# 2021-06-24.net
KiCad netlist of a schematic drawn in EasyEDA
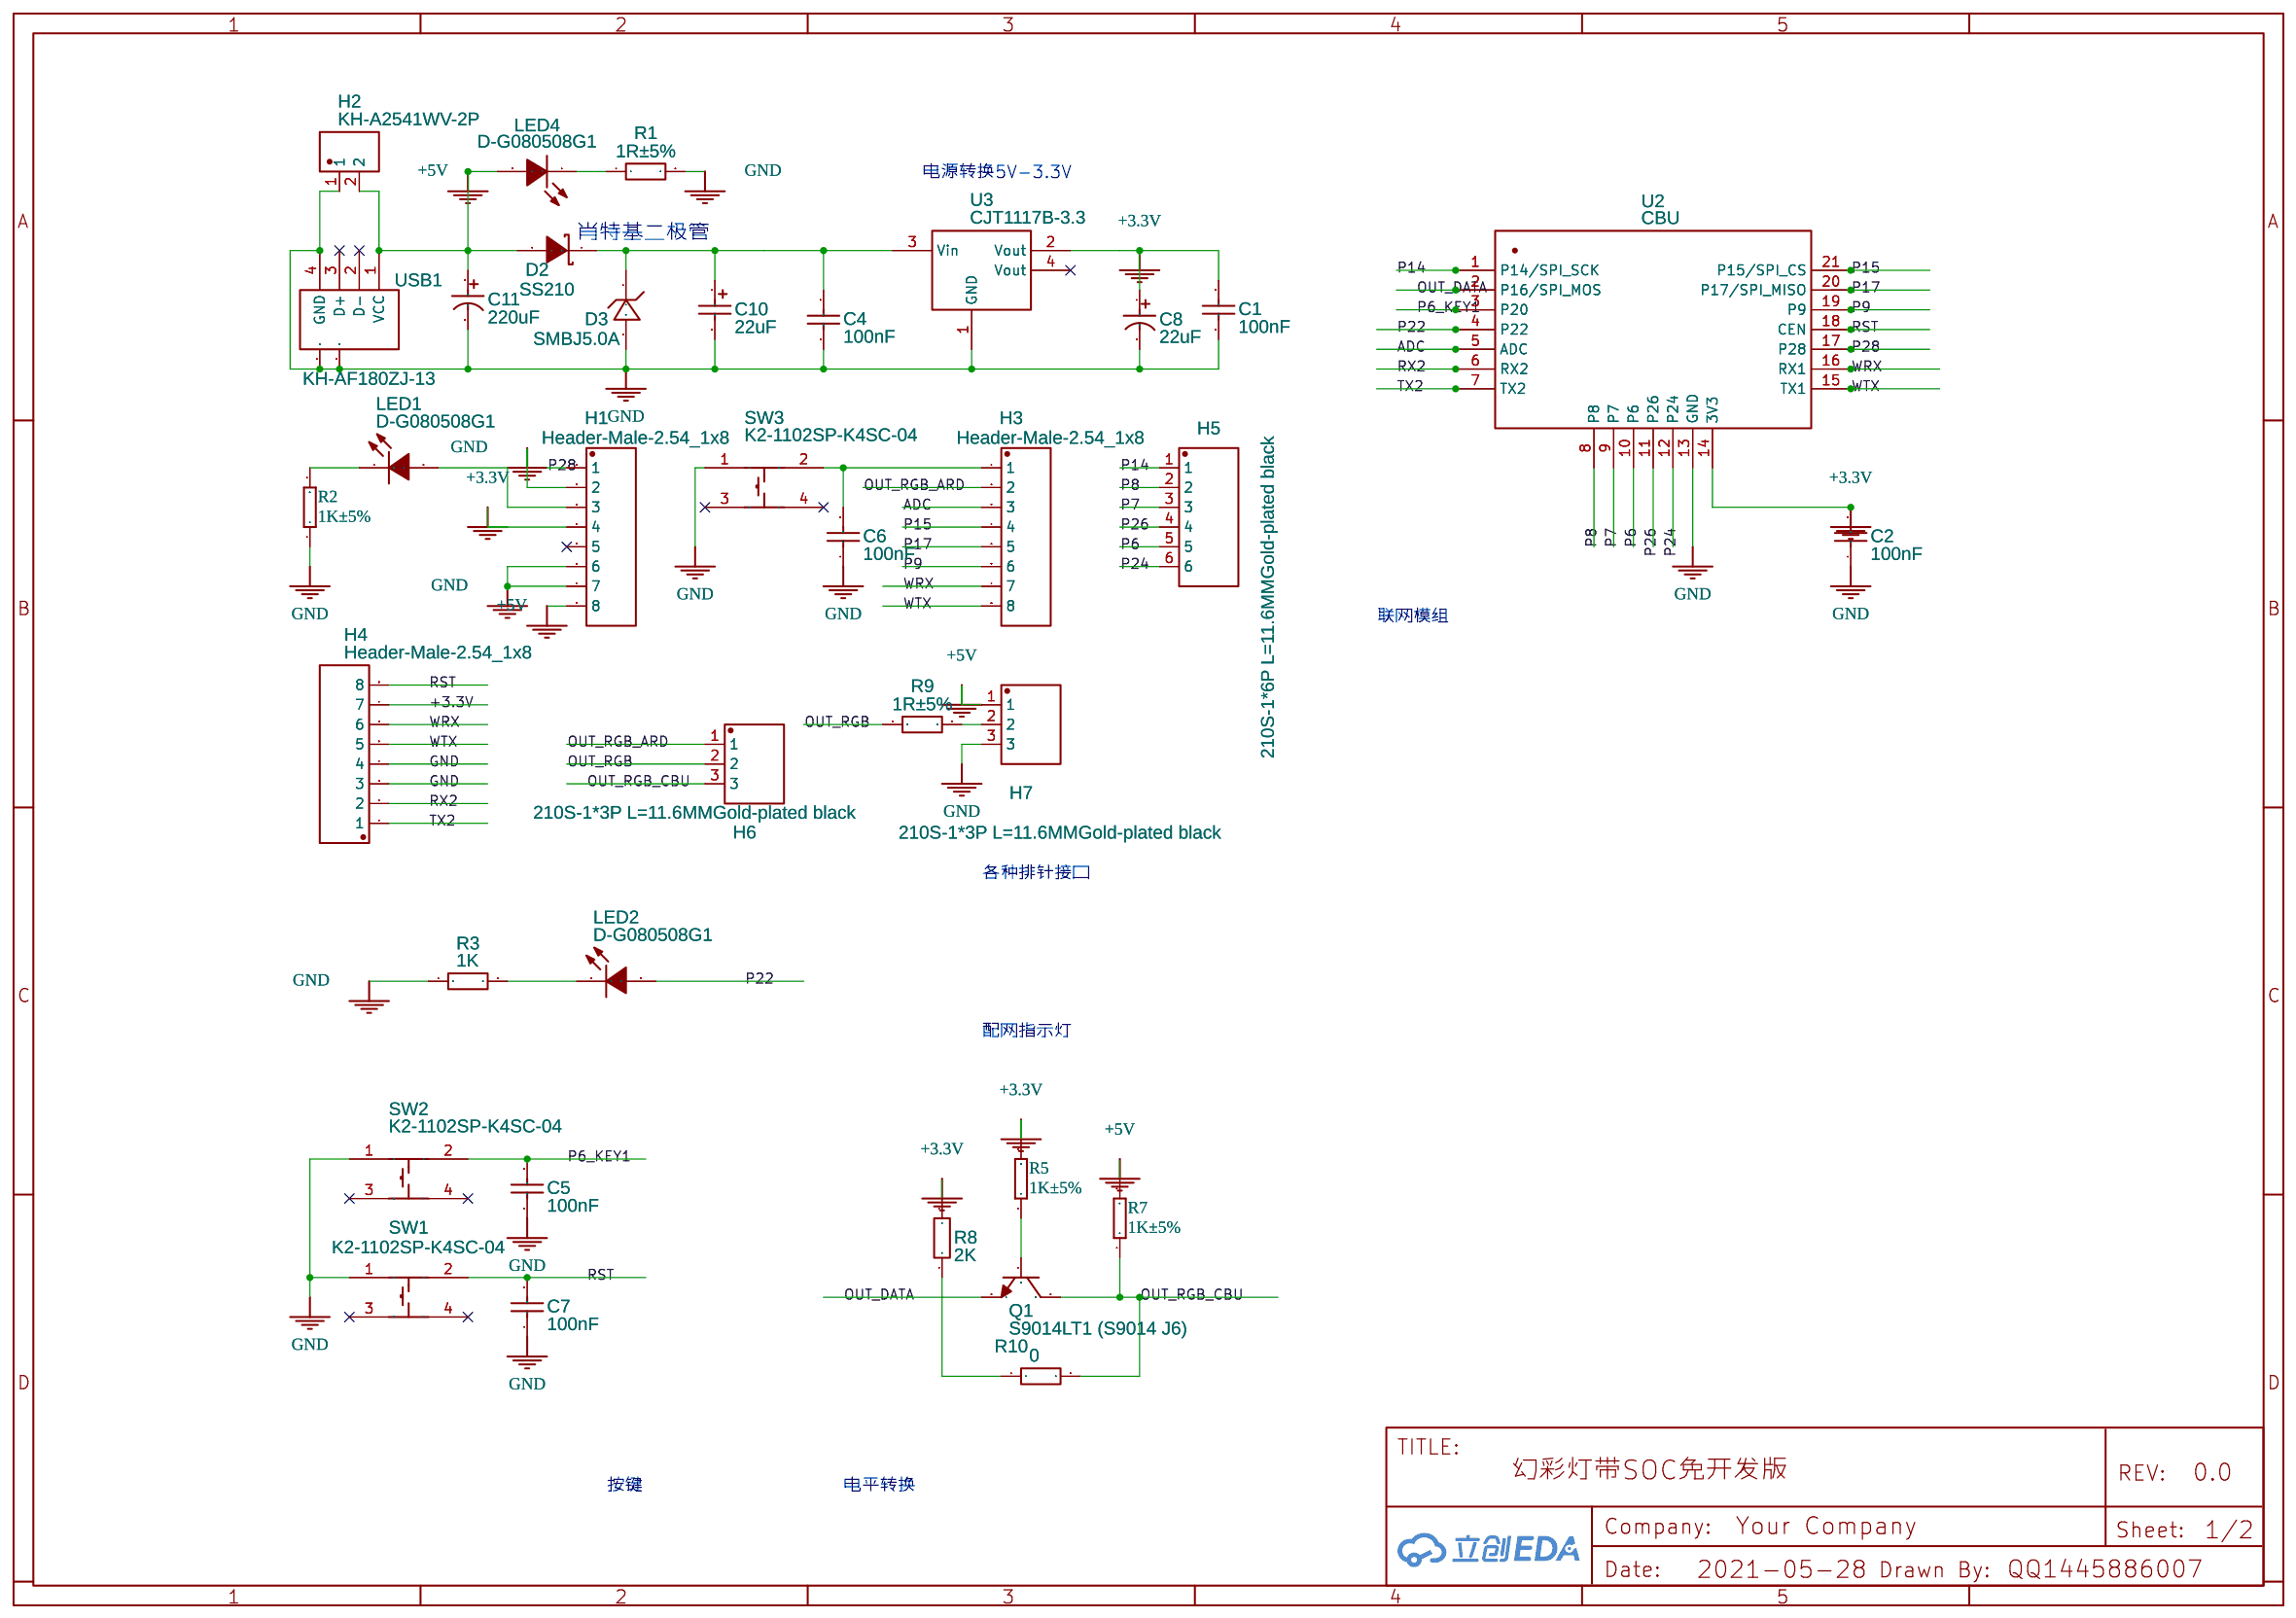
[diagram p0: schematic sheet]

(export (version "E")
  (design (tool "Eeschema 10.0.6"))
  (components
    (comp (ref "C1")
      (value "100nF")
      (fields
        (field (name "BOM_Manufacturer Part") "CL10F104ZA8NNNC")
        (field (name "BOM_Supplier Part") "C95838")
      )
      (libsource (lib "") (part "CL10F104ZA8NNNC"))
    )
    (comp (ref "C2")
      (value "100nF")
      (fields
        (field (name "BOM_Manufacturer Part") "CL10F104ZA8NNNC")
        (field (name "BOM_Supplier Part") "C95838")
      )
      (libsource (lib "") (part "CL10F104ZA8NNNC"))
    )
    (comp (ref "C4")
      (value "100nF")
      (fields
        (field (name "BOM_Manufacturer Part") "CL10F104ZA8NNNC")
        (field (name "BOM_Supplier Part") "C95838")
      )
      (libsource (lib "") (part "CL10F104ZA8NNNC"))
    )
    (comp (ref "C5")
      (value "100nF")
      (fields
        (field (name "BOM_Manufacturer Part") "CL10F104ZA8NNNC")
        (field (name "BOM_Supplier Part") "C95838")
      )
      (libsource (lib "") (part "CL10F104ZA8NNNC"))
    )
    (comp (ref "C6")
      (value "100nF")
      (fields
        (field (name "BOM_Manufacturer Part") "CL10F104ZA8NNNC")
        (field (name "BOM_Supplier Part") "C95838")
      )
      (libsource (lib "") (part "CL10F104ZA8NNNC"))
    )
    (comp (ref "C7")
      (value "100nF")
      (fields
        (field (name "BOM_Manufacturer Part") "CL10F104ZA8NNNC")
        (field (name "BOM_Supplier Part") "C95838")
      )
      (libsource (lib "") (part "CL10F104ZA8NNNC"))
    )
    (comp (ref "C8")
      (value "22uF")
      (fields
        (field (name "BOM_Manufacturer Part") "KS1C220MB070A00CV0")
        (field (name "BOM_Supplier Part") "C216316")
      )
      (libsource (lib "") (part "KS1C220MB070A00CV0"))
    )
    (comp (ref "C10")
      (value "22uF")
      (fields
        (field (name "BOM_Manufacturer Part") "CA45-B010K226T")
        (field (name "BOM_Supplier Part") "C122758")
      )
      (libsource (lib "") (part "CA45-B010K226T"))
    )
    (comp (ref "C11")
      (value "220uF")
      (fields
        (field (name "BOM_Manufacturer Part") "220uF 10V 6.3*7")
        (field (name "BOM_Supplier Part") "C43331")
      )
      (libsource (lib "") (part "220uF 10V 6.3*7"))
    )
    (comp (ref "D2")
      (value "SS210")
      (fields (field (name "BOM_Supplier Part") "C84030"))
      (libsource (lib "") (part "SS210_C84030"))
    )
    (comp (ref "D3")
      (value "SMBJ5.0A")
      (fields (field (name "BOM_Supplier Part") "C169448"))
      (libsource (lib "") (part "SMBJ5.0A_C169448"))
    )
    (comp (ref "H1")
      (value "Header-Male-2.54_1x8")
      (fields
        (field (name "BOM_Manufacturer Part") "210S-1*8P L=11.6MMGold-plated black")
        (field (name "BOM_Supplier Part") "C124381")
      )
      (libsource (lib "") (part "Header-Male-2.54_1x8"))
    )
    (comp (ref "H2")
      (value "KH-A2541WV-2P")
      (fields (field (name "BOM_Supplier Part") "C2833329"))
      (libsource (lib "") (part "KH-A2541WV-2P"))
    )
    (comp (ref "H3")
      (value "Header-Male-2.54_1x8")
      (fields
        (field (name "BOM_Manufacturer Part") "210S-1*8P L=11.6MMGold-plated black")
        (field (name "BOM_Supplier Part") "C124381")
      )
      (libsource (lib "") (part "Header-Male-2.54_1x8"))
    )
    (comp (ref "H4")
      (value "Header-Male-2.54_1x8")
      (fields
        (field (name "BOM_Manufacturer Part") "210S-1*8P L=11.6MMGold-plated black")
        (field (name "BOM_Supplier Part") "C124381")
      )
      (libsource (lib "") (part "Header-Male-2.54_1x8_1"))
    )
    (comp (ref "H5")
      (value "210S-1*6P L=11.6MMGold-plated black")
      (fields (field (name "BOM_Supplier Part") "C124380"))
      (libsource (lib "") (part "210S-1*6P L=11.6MMGold-plated black"))
    )
    (comp (ref "H6")
      (value "210S-1*3P L=11.6MMGold-plated black")
      (fields (field (name "BOM_Supplier Part") "C124376"))
      (libsource (lib "") (part "210S-1*3P L=11.6MMGold-plated black"))
    )
    (comp (ref "H7")
      (value "210S-1*3P L=11.6MMGold-plated black")
      (fields (field (name "BOM_Supplier Part") "C124376"))
      (libsource (lib "") (part "210S-1*3P L=11.6MMGold-plated black"))
    )
    (comp (ref "LED1")
      (value "D-G080508G1")
      (fields (field (name "BOM_Supplier Part") "C107402"))
      (libsource (lib "") (part "D-G080508G1"))
    )
    (comp (ref "LED2")
      (value "D-G080508G1")
      (fields (field (name "BOM_Supplier Part") "C107402"))
      (libsource (lib "") (part "D-G080508G1"))
    )
    (comp (ref "LED4")
      (value "D-G080508G1")
      (fields (field (name "BOM_Supplier Part") "C107402"))
      (libsource (lib "") (part "D-G080508G1_1"))
    )
    (comp (ref "Q1")
      (value "S9014LT1 (S9014 J6)")
      (fields (field (name "BOM_Supplier Part") "C2148"))
      (libsource (lib "") (part "S9014LT1 (S9014 J6)"))
    )
    (comp (ref "R1")
      (value "1R±5%")
      (fields
        (field (name "BOM_Manufacturer Part") "0603WAJ010JT5E")
        (field (name "BOM_Supplier Part") "C25212")
      )
      (libsource (lib "") (part "0603WAJ010JT5E"))
    )
    (comp (ref "R2") (value "1K±5%") (libsource (lib "") (part "Unknown_40_-530")))
    (comp (ref "R3")
      (value "1K")
      (fields
        (field (name "BOM_Manufacturer Part") "RK73B1JTTD102J")
        (field (name "BOM_Supplier Part") "C131707")
      )
      (libsource (lib "") (part "RK73B1JTTD102J"))
    )
    (comp (ref "R5") (value "1K±5%") (libsource (lib "") (part "Unknown_400_-190")))
    (comp (ref "R7") (value "1K±5%") (libsource (lib "") (part "Unknown_450_-170")))
    (comp (ref "R8")
      (value "2K")
      (fields
        (field (name "BOM_Manufacturer Part") "RM06FTN2001")
        (field (name "BOM_Supplier Part") "C114806")
      )
      (libsource (lib "") (part "RM06FTN2001"))
    )
    (comp (ref "R9")
      (value "1R±5%")
      (fields
        (field (name "BOM_Manufacturer Part") "0603WAJ010JT5E")
        (field (name "BOM_Supplier Part") "C25212")
      )
      (libsource (lib "") (part "0603WAJ010JT5E"))
    )
    (comp (ref "R10")
      (value "0")
      (fields (field (name "BOM_Manufacturer Part") "RM06JTN0") (field (name "BOM_Supplier Part") "C188117"))
      (libsource (lib "") (part "RM06JTN0"))
    )
    (comp (ref "SW1")
      (value "K2-1102SP-K4SC-04")
      (fields (field (name "BOM_Supplier Part") "C129461"))
      (libsource (lib "") (part "K2-1102SP-K4SC-04"))
    )
    (comp (ref "SW2")
      (value "K2-1102SP-K4SC-04")
      (fields (field (name "BOM_Supplier Part") "C129461"))
      (libsource (lib "") (part "K2-1102SP-K4SC-04"))
    )
    (comp (ref "SW3")
      (value "K2-1102SP-K4SC-04")
      (fields (field (name "BOM_Supplier Part") "C129461"))
      (libsource (lib "") (part "K2-1102SP-K4SC-04"))
    )
    (comp (ref "U2") (value "CBU") (libsource (lib "") (part "CBU")))
    (comp (ref "U3")
      (value "CJT1117B-3.3")
      (fields (field (name "BOM_Supplier Part") "C78777"))
      (libsource (lib "") (part "CJT1117B-3.3"))
    )
    (comp (ref "USB1")
      (value "KH-AF180ZJ-13")
      (fields (field (name "BOM_Supplier Part") "C2833344"))
      (libsource (lib "") (part "KH-AF180ZJ-13"))
    )
  )
  (nets
    (net (code "1") (name "+3.3V") (class "Default")
      (node (ref "C1") (pin "2") (pinfunction "2_2") (pintype "input"))
      (node (ref "C2") (pin "2") (pinfunction "2_2") (pintype "input"))
      (node (ref "C8") (pin "1") (pinfunction "1_1") (pintype "input"))
      (node (ref "H1") (pin "4") (pinfunction "4_4") (pintype "unspecified"))
      (node (ref "H4") (pin "7") (pinfunction "7_7") (pintype "unspecified"))
      (node (ref "R5") (pin "2") (pinfunction "2_2") (pintype "unspecified"))
      (node (ref "R8") (pin "1") (pinfunction "1_1") (pintype "unspecified"))
      (node (ref "U2") (pin "14") (pinfunction "3V3_14") (pintype "unspecified"))
      (node (ref "U3") (pin "2") (pinfunction "Vout_2") (pintype "unspecified"))
    )
    (net (code "2") (name "+5V") (class "Default")
      (node (ref "C11") (pin "1") (pinfunction "1_1") (pintype "input"))
      (node (ref "D2") (pin "2") (pinfunction "A_2") (pintype "unspecified"))
      (node (ref "H1") (pin "8") (pinfunction "8_8") (pintype "unspecified"))
      (node (ref "H2") (pin "2") (pinfunction "2_2") (pintype "unspecified"))
      (node (ref "H7") (pin "1") (pinfunction "1_1") (pintype "unspecified"))
      (node (ref "LED4") (pin "2") (pinfunction "A_2") (pintype "unspecified"))
      (node (ref "R7") (pin "2") (pinfunction "2_2") (pintype "unspecified"))
      (node (ref "USB1") (pin "1") (pinfunction "VCC_1") (pintype "unspecified"))
    )
    (net (code "3") (name "/ADC") (class "Default")
      (node (ref "H3") (pin "3") (pinfunction "3_3") (pintype "unspecified"))
      (node (ref "U2") (pin "5") (pinfunction "ADC_5") (pintype "unspecified"))
    )
    (net (code "4") (name "/OUT_DATA") (class "Default")
      (node (ref "Q1") (pin "2") (pinfunction "E_2") (pintype "unspecified"))
      (node (ref "R10") (pin "1") (pinfunction "1_1") (pintype "unspecified"))
      (node (ref "R8") (pin "2") (pinfunction "2_2") (pintype "unspecified"))
      (node (ref "U2") (pin "2") (pinfunction "P16/SPI_MOS_2") (pintype "unspecified"))
    )
    (net (code "5") (name "/OUT_RGB") (class "Default")
      (node (ref "H6") (pin "2") (pinfunction "2_2") (pintype "unspecified"))
      (node (ref "R9") (pin "1") (pinfunction "1_1") (pintype "input"))
    )
    (net (code "6") (name "/OUT_RGB_ARD") (class "Default")
      (node (ref "H3") (pin "2") (pinfunction "2_2") (pintype "unspecified"))
      (node (ref "H6") (pin "1") (pinfunction "1_1") (pintype "unspecified"))
    )
    (net (code "7") (name "/OUT_RGB_CBU") (class "Default")
      (node (ref "H6") (pin "3") (pinfunction "3_3") (pintype "unspecified"))
      (node (ref "Q1") (pin "3") (pinfunction "C_3") (pintype "unspecified"))
      (node (ref "R10") (pin "2") (pinfunction "2_2") (pintype "unspecified"))
      (node (ref "R7") (pin "1") (pinfunction "1_1") (pintype "unspecified"))
    )
    (net (code "8") (name "/P6") (class "Default")
      (node (ref "H5") (pin "5") (pinfunction "5_5") (pintype "unspecified"))
      (node (ref "U2") (pin "10") (pinfunction "P6_10") (pintype "unspecified"))
    )
    (net (code "9") (name "/P6_KEY1") (class "Default")
      (node (ref "C5") (pin "2") (pinfunction "2_2") (pintype "input"))
      (node (ref "SW2") (pin "2") (pinfunction "2_2") (pintype "unspecified"))
      (node (ref "U2") (pin "3") (pinfunction "P20_3") (pintype "unspecified"))
    )
    (net (code "10") (name "/P7") (class "Default")
      (node (ref "H5") (pin "3") (pinfunction "3_3") (pintype "unspecified"))
      (node (ref "U2") (pin "9") (pinfunction "P7_9") (pintype "unspecified"))
    )
    (net (code "11") (name "/P8") (class "Default")
      (node (ref "H5") (pin "2") (pinfunction "2_2") (pintype "unspecified"))
      (node (ref "U2") (pin "8") (pinfunction "P8_8") (pintype "unspecified"))
    )
    (net (code "12") (name "/P9") (class "Default")
      (node (ref "H3") (pin "6") (pinfunction "6_6") (pintype "unspecified"))
      (node (ref "U2") (pin "19") (pinfunction "P9_19") (pintype "unspecified"))
    )
    (net (code "13") (name "/P14") (class "Default")
      (node (ref "H5") (pin "1") (pinfunction "1_1") (pintype "unspecified"))
      (node (ref "U2") (pin "1") (pinfunction "P14/SPI_SCK_1") (pintype "unspecified"))
    )
    (net (code "14") (name "/P15") (class "Default")
      (node (ref "H3") (pin "4") (pinfunction "4_4") (pintype "unspecified"))
      (node (ref "U2") (pin "21") (pinfunction "P15/SPI_CS_21") (pintype "unspecified"))
    )
    (net (code "15") (name "/P17") (class "Default")
      (node (ref "H3") (pin "5") (pinfunction "5_5") (pintype "unspecified"))
      (node (ref "U2") (pin "20") (pinfunction "P17/SPI_MISO_20") (pintype "unspecified"))
    )
    (net (code "16") (name "/P22") (class "Default")
      (node (ref "LED2") (pin "2") (pinfunction "A_2") (pintype "unspecified"))
      (node (ref "U2") (pin "4") (pinfunction "P22_4") (pintype "unspecified"))
    )
    (net (code "17") (name "/P24") (class "Default")
      (node (ref "H5") (pin "6") (pinfunction "6_6") (pintype "unspecified"))
      (node (ref "U2") (pin "12") (pinfunction "P24_12") (pintype "unspecified"))
    )
    (net (code "18") (name "/P26") (class "Default")
      (node (ref "H5") (pin "4") (pinfunction "4_4") (pintype "unspecified"))
      (node (ref "U2") (pin "11") (pinfunction "P26_11") (pintype "unspecified"))
    )
    (net (code "19") (name "/P28") (class "Default")
      (node (ref "H1") (pin "1") (pinfunction "1_1") (pintype "unspecified"))
      (node (ref "U2") (pin "17") (pinfunction "P28_17") (pintype "unspecified"))
    )
    (net (code "20") (name "/RST") (class "Default")
      (node (ref "C7") (pin "2") (pinfunction "2_2") (pintype "input"))
      (node (ref "H4") (pin "8") (pinfunction "8_8") (pintype "unspecified"))
      (node (ref "SW1") (pin "2") (pinfunction "2_2") (pintype "unspecified"))
      (node (ref "U2") (pin "18") (pinfunction "CEN_18") (pintype "unspecified"))
    )
    (net (code "21") (name "/RX2") (class "Default")
      (node (ref "H4") (pin "2") (pinfunction "2_2") (pintype "unspecified"))
      (node (ref "U2") (pin "6") (pinfunction "RX2_6") (pintype "unspecified"))
    )
    (net (code "22") (name "/TX2") (class "Default")
      (node (ref "H4") (pin "1") (pinfunction "1_1") (pintype "unspecified"))
      (node (ref "U2") (pin "7") (pinfunction "TX2_7") (pintype "unspecified"))
    )
    (net (code "23") (name "/WRX") (class "Default")
      (node (ref "H3") (pin "7") (pinfunction "7_7") (pintype "unspecified"))
      (node (ref "H4") (pin "6") (pinfunction "6_6") (pintype "unspecified"))
      (node (ref "U2") (pin "16") (pinfunction "RX1_16") (pintype "unspecified"))
    )
    (net (code "24") (name "/WTX") (class "Default")
      (node (ref "H3") (pin "8") (pinfunction "8_8") (pintype "unspecified"))
      (node (ref "H4") (pin "5") (pinfunction "5_5") (pintype "unspecified"))
      (node (ref "U2") (pin "15") (pinfunction "TX1_15") (pintype "unspecified"))
    )
    (net (code "25") (name "GND") (class "Default")
      (node (ref "C1") (pin "1") (pinfunction "1_1") (pintype "input"))
      (node (ref "C10") (pin "2") (pinfunction "2_2") (pintype "input"))
      (node (ref "C11") (pin "2") (pinfunction "2_2") (pintype "input"))
      (node (ref "C2") (pin "1") (pinfunction "1_1") (pintype "input"))
      (node (ref "C4") (pin "1") (pinfunction "1_1") (pintype "input"))
      (node (ref "C5") (pin "1") (pinfunction "1_1") (pintype "input"))
      (node (ref "C6") (pin "1") (pinfunction "1_1") (pintype "input"))
      (node (ref "C7") (pin "1") (pinfunction "1_1") (pintype "input"))
      (node (ref "C8") (pin "2") (pinfunction "2_2") (pintype "input"))
      (node (ref "D3") (pin "2") (pinfunction "2_2") (pintype "unspecified"))
      (node (ref "H1") (pin "2") (pinfunction "2_2") (pintype "unspecified"))
      (node (ref "H1") (pin "6") (pinfunction "6_6") (pintype "unspecified"))
      (node (ref "H1") (pin "7") (pinfunction "7_7") (pintype "unspecified"))
      (node (ref "H2") (pin "1") (pinfunction "1_1") (pintype "unspecified"))
      (node (ref "H4") (pin "3") (pinfunction "3_3") (pintype "unspecified"))
      (node (ref "H4") (pin "4") (pinfunction "4_4") (pintype "unspecified"))
      (node (ref "H7") (pin "3") (pinfunction "3_3") (pintype "unspecified"))
      (node (ref "R1") (pin "2") (pinfunction "2_2") (pintype "input"))
      (node (ref "R2") (pin "1") (pinfunction "1_1") (pintype "unspecified"))
      (node (ref "R3") (pin "1") (pinfunction "1_1") (pintype "input"))
      (node (ref "SW1") (pin "1") (pinfunction "1_1") (pintype "unspecified"))
      (node (ref "SW2") (pin "1") (pinfunction "1_1") (pintype "unspecified"))
      (node (ref "SW3") (pin "1") (pinfunction "1_1") (pintype "unspecified"))
      (node (ref "U2") (pin "13") (pinfunction "GND_13") (pintype "unspecified"))
      (node (ref "U3") (pin "1") (pinfunction "GND_1") (pintype "unspecified"))
      (node (ref "USB1") (pin "4") (pinfunction "GND_4") (pintype "unspecified"))
      (node (ref "USB1") (pin "5") (pinfunction "5_5") (pintype "unspecified"))
      (node (ref "USB1") (pin "6") (pinfunction "6_6") (pintype "unspecified"))
    )
    (net (code "26") (name "Net-(C6-Pad2)") (class "Default")
      (node (ref "C6") (pin "2") (pinfunction "2_2") (pintype "input"))
      (node (ref "H3") (pin "1") (pinfunction "1_1") (pintype "unspecified"))
      (node (ref "SW3") (pin "2") (pinfunction "2_2") (pintype "unspecified"))
    )
    (net (code "27") (name "Net-(D2-C)") (class "Default")
      (node (ref "C10") (pin "1") (pinfunction "1_1") (pintype "input"))
      (node (ref "C4") (pin "2") (pinfunction "2_2") (pintype "input"))
      (node (ref "D2") (pin "1") (pinfunction "C_1") (pintype "unspecified"))
      (node (ref "D3") (pin "1") (pinfunction "1_1") (pintype "unspecified"))
      (node (ref "U3") (pin "3") (pinfunction "Vin_3") (pintype "unspecified"))
    )
    (net (code "28") (name "Net-(H7-Pad2)") (class "Default")
      (node (ref "H7") (pin "2") (pinfunction "2_2") (pintype "unspecified"))
      (node (ref "R9") (pin "2") (pinfunction "2_2") (pintype "input"))
    )
    (net (code "29") (name "Net-(LED1-A)") (class "Default")
      (node (ref "H1") (pin "3") (pinfunction "3_3") (pintype "unspecified"))
      (node (ref "LED1") (pin "2") (pinfunction "A_2") (pintype "unspecified"))
    )
    (net (code "30") (name "Net-(LED1-K)") (class "Default")
      (node (ref "LED1") (pin "1") (pinfunction "K_1") (pintype "unspecified"))
      (node (ref "R2") (pin "2") (pinfunction "2_2") (pintype "unspecified"))
    )
    (net (code "31") (name "Net-(LED2-K)") (class "Default")
      (node (ref "LED2") (pin "1") (pinfunction "K_1") (pintype "unspecified"))
      (node (ref "R3") (pin "2") (pinfunction "2_2") (pintype "input"))
    )
    (net (code "32") (name "Net-(LED4-K)") (class "Default")
      (node (ref "LED4") (pin "1") (pinfunction "K_1") (pintype "unspecified"))
      (node (ref "R1") (pin "1") (pinfunction "1_1") (pintype "input"))
    )
    (net (code "33") (name "Net-(Q1-B)") (class "Default")
      (node (ref "Q1") (pin "1") (pinfunction "B_1") (pintype "unspecified"))
      (node (ref "R5") (pin "1") (pinfunction "1_1") (pintype "unspecified"))
    )
    (net (code "34") (name "unconnected-(H1-Pad5)") (class "Default")
      (node (ref "H1") (pin "5") (pinfunction "5_5") (pintype "unspecified+no_connect"))
    )
    (net (code "35") (name "unconnected-(SW1-Pad3)") (class "Default")
      (node (ref "SW1") (pin "3") (pinfunction "3_3") (pintype "unspecified+no_connect"))
    )
    (net (code "36") (name "unconnected-(SW1-Pad4)") (class "Default")
      (node (ref "SW1") (pin "4") (pinfunction "4_4") (pintype "unspecified+no_connect"))
    )
    (net (code "37") (name "unconnected-(SW2-Pad3)") (class "Default")
      (node (ref "SW2") (pin "3") (pinfunction "3_3") (pintype "unspecified+no_connect"))
    )
    (net (code "38") (name "unconnected-(SW2-Pad4)") (class "Default")
      (node (ref "SW2") (pin "4") (pinfunction "4_4") (pintype "unspecified+no_connect"))
    )
    (net (code "39") (name "unconnected-(SW3-Pad3)") (class "Default")
      (node (ref "SW3") (pin "3") (pinfunction "3_3") (pintype "unspecified+no_connect"))
    )
    (net (code "40") (name "unconnected-(SW3-Pad4)") (class "Default")
      (node (ref "SW3") (pin "4") (pinfunction "4_4") (pintype "unspecified+no_connect"))
    )
    (net (code "41") (name "unconnected-(U3-Vout-Pad4)") (class "Default")
      (node (ref "U3") (pin "4") (pinfunction "Vout_4") (pintype "unspecified+no_connect"))
    )
    (net (code "42") (name "unconnected-(USB1-D+-Pad3)") (class "Default")
      (node (ref "USB1") (pin "3") (pinfunction "D+_3") (pintype "unspecified+no_connect"))
    )
    (net (code "43") (name "unconnected-(USB1-D--Pad2)") (class "Default")
      (node (ref "USB1") (pin "2") (pinfunction "D-_2") (pintype "unspecified+no_connect"))
    )
  )
)
